# Lixieuhr_Master.net
KiCad netlist of a schematic drawn in EAGLE
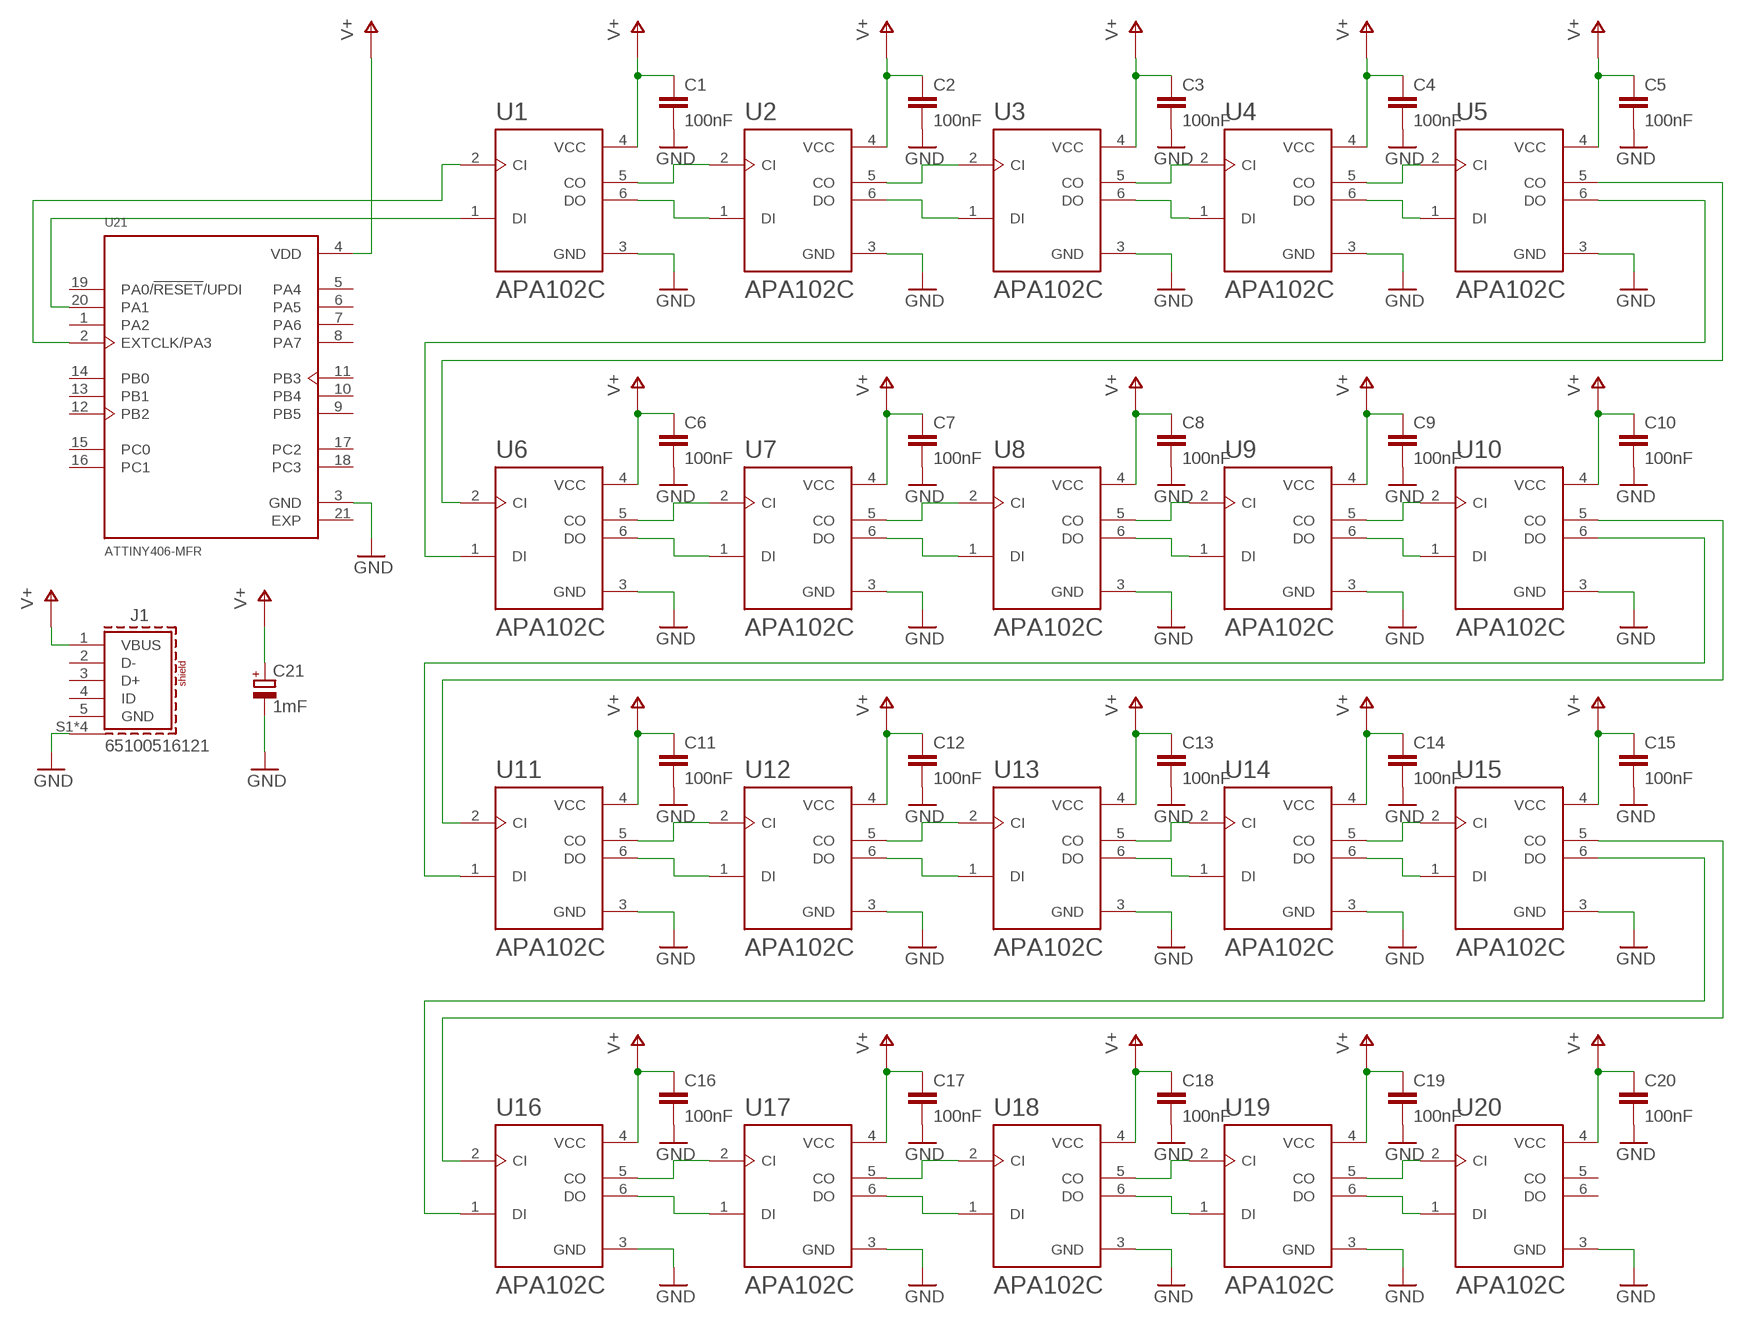
[diagram p0: schematic, sheet 1]

(export (version "E")
  (design (tool "Eeschema 10.0.6"))
  (components
    (comp (ref "C1")
      (value "100nF")
      (footprint "eagle-import:C0805")
      (libsource (lib "eagle-import") (part "C-0805"))
    )
    (comp (ref "C2")
      (value "100nF")
      (footprint "eagle-import:C0805")
      (libsource (lib "eagle-import") (part "C-0805"))
    )
    (comp (ref "C3")
      (value "100nF")
      (footprint "eagle-import:C0805")
      (libsource (lib "eagle-import") (part "C-0805"))
    )
    (comp (ref "C4")
      (value "100nF")
      (footprint "eagle-import:C0805")
      (libsource (lib "eagle-import") (part "C-0805"))
    )
    (comp (ref "C5")
      (value "100nF")
      (footprint "eagle-import:C0805")
      (libsource (lib "eagle-import") (part "C-0805"))
    )
    (comp (ref "C6")
      (value "100nF")
      (footprint "eagle-import:C0805")
      (libsource (lib "eagle-import") (part "C-0805"))
    )
    (comp (ref "C7")
      (value "100nF")
      (footprint "eagle-import:C0805")
      (libsource (lib "eagle-import") (part "C-0805"))
    )
    (comp (ref "C8")
      (value "100nF")
      (footprint "eagle-import:C0805")
      (libsource (lib "eagle-import") (part "C-0805"))
    )
    (comp (ref "C9")
      (value "100nF")
      (footprint "eagle-import:C0805")
      (libsource (lib "eagle-import") (part "C-0805"))
    )
    (comp (ref "C10")
      (value "100nF")
      (footprint "eagle-import:C0805")
      (libsource (lib "eagle-import") (part "C-0805"))
    )
    (comp (ref "C11")
      (value "100nF")
      (footprint "eagle-import:C0805")
      (libsource (lib "eagle-import") (part "C-0805"))
    )
    (comp (ref "C12")
      (value "100nF")
      (footprint "eagle-import:C0805")
      (libsource (lib "eagle-import") (part "C-0805"))
    )
    (comp (ref "C13")
      (value "100nF")
      (footprint "eagle-import:C0805")
      (libsource (lib "eagle-import") (part "C-0805"))
    )
    (comp (ref "C14")
      (value "100nF")
      (footprint "eagle-import:C0805")
      (libsource (lib "eagle-import") (part "C-0805"))
    )
    (comp (ref "C15")
      (value "100nF")
      (footprint "eagle-import:C0805")
      (libsource (lib "eagle-import") (part "C-0805"))
    )
    (comp (ref "C16")
      (value "100nF")
      (footprint "eagle-import:C0805")
      (libsource (lib "eagle-import") (part "C-0805"))
    )
    (comp (ref "C17")
      (value "100nF")
      (footprint "eagle-import:C0805")
      (libsource (lib "eagle-import") (part "C-0805"))
    )
    (comp (ref "C18")
      (value "100nF")
      (footprint "eagle-import:C0805")
      (libsource (lib "eagle-import") (part "C-0805"))
    )
    (comp (ref "C19")
      (value "100nF")
      (footprint "eagle-import:C0805")
      (libsource (lib "eagle-import") (part "C-0805"))
    )
    (comp (ref "C20")
      (value "100nF")
      (footprint "eagle-import:C0805")
      (libsource (lib "eagle-import") (part "C-0805"))
    )
    (comp (ref "C21")
      (value "1mF")
      (footprint "eagle-import:E5-8,5")
      (libsource (lib "eagle-import") (part "CPOL-EUE5-8.5"))
    )
    (comp (ref "J1")
      (value "65100516121")
      (footprint "eagle-import:65100516121")
      (fields (field (name "MF") "Würth Elektronik"))
      (libsource (lib "eagle-import") (part "65100516121"))
    )
    (comp (ref "U1")
      (value "APA102C")
      (footprint "eagle-import:SON160P500X500X140-6N")
      (fields (field (name "MF") "Shiji Lighting"))
      (libsource (lib "eagle-import") (part "APA102C"))
    )
    (comp (ref "U2")
      (value "APA102C")
      (footprint "eagle-import:SON160P500X500X140-6N")
      (fields (field (name "MF") "Shiji Lighting"))
      (libsource (lib "eagle-import") (part "APA102C"))
    )
    (comp (ref "U3")
      (value "APA102C")
      (footprint "eagle-import:SON160P500X500X140-6N")
      (fields (field (name "MF") "Shiji Lighting"))
      (libsource (lib "eagle-import") (part "APA102C"))
    )
    (comp (ref "U4")
      (value "APA102C")
      (footprint "eagle-import:SON160P500X500X140-6N")
      (fields (field (name "MF") "Shiji Lighting"))
      (libsource (lib "eagle-import") (part "APA102C"))
    )
    (comp (ref "U5")
      (value "APA102C")
      (footprint "eagle-import:SON160P500X500X140-6N")
      (fields (field (name "MF") "Shiji Lighting"))
      (libsource (lib "eagle-import") (part "APA102C"))
    )
    (comp (ref "U6")
      (value "APA102C")
      (footprint "eagle-import:SON160P500X500X140-6N")
      (fields (field (name "MF") "Shiji Lighting"))
      (libsource (lib "eagle-import") (part "APA102C"))
    )
    (comp (ref "U7")
      (value "APA102C")
      (footprint "eagle-import:SON160P500X500X140-6N")
      (fields (field (name "MF") "Shiji Lighting"))
      (libsource (lib "eagle-import") (part "APA102C"))
    )
    (comp (ref "U8")
      (value "APA102C")
      (footprint "eagle-import:SON160P500X500X140-6N")
      (fields (field (name "MF") "Shiji Lighting"))
      (libsource (lib "eagle-import") (part "APA102C"))
    )
    (comp (ref "U9")
      (value "APA102C")
      (footprint "eagle-import:SON160P500X500X140-6N")
      (fields (field (name "MF") "Shiji Lighting"))
      (libsource (lib "eagle-import") (part "APA102C"))
    )
    (comp (ref "U10")
      (value "APA102C")
      (footprint "eagle-import:SON160P500X500X140-6N")
      (fields (field (name "MF") "Shiji Lighting"))
      (libsource (lib "eagle-import") (part "APA102C"))
    )
    (comp (ref "U11")
      (value "APA102C")
      (footprint "eagle-import:SON160P500X500X140-6N")
      (fields (field (name "MF") "Shiji Lighting"))
      (libsource (lib "eagle-import") (part "APA102C"))
    )
    (comp (ref "U12")
      (value "APA102C")
      (footprint "eagle-import:SON160P500X500X140-6N")
      (fields (field (name "MF") "Shiji Lighting"))
      (libsource (lib "eagle-import") (part "APA102C"))
    )
    (comp (ref "U13")
      (value "APA102C")
      (footprint "eagle-import:SON160P500X500X140-6N")
      (fields (field (name "MF") "Shiji Lighting"))
      (libsource (lib "eagle-import") (part "APA102C"))
    )
    (comp (ref "U14")
      (value "APA102C")
      (footprint "eagle-import:SON160P500X500X140-6N")
      (fields (field (name "MF") "Shiji Lighting"))
      (libsource (lib "eagle-import") (part "APA102C"))
    )
    (comp (ref "U15")
      (value "APA102C")
      (footprint "eagle-import:SON160P500X500X140-6N")
      (fields (field (name "MF") "Shiji Lighting"))
      (libsource (lib "eagle-import") (part "APA102C"))
    )
    (comp (ref "U16")
      (value "APA102C")
      (footprint "eagle-import:SON160P500X500X140-6N")
      (fields (field (name "MF") "Shiji Lighting"))
      (libsource (lib "eagle-import") (part "APA102C"))
    )
    (comp (ref "U17")
      (value "APA102C")
      (footprint "eagle-import:SON160P500X500X140-6N")
      (fields (field (name "MF") "Shiji Lighting"))
      (libsource (lib "eagle-import") (part "APA102C"))
    )
    (comp (ref "U18")
      (value "APA102C")
      (footprint "eagle-import:SON160P500X500X140-6N")
      (fields (field (name "MF") "Shiji Lighting"))
      (libsource (lib "eagle-import") (part "APA102C"))
    )
    (comp (ref "U19")
      (value "APA102C")
      (footprint "eagle-import:SON160P500X500X140-6N")
      (fields (field (name "MF") "Shiji Lighting"))
      (libsource (lib "eagle-import") (part "APA102C"))
    )
    (comp (ref "U20")
      (value "APA102C")
      (footprint "eagle-import:SON160P500X500X140-6N")
      (fields (field (name "MF") "Shiji Lighting"))
      (libsource (lib "eagle-import") (part "APA102C"))
    )
    (comp (ref "U21")
      (value "ATTINY406-MFR")
      (footprint "eagle-import:QFN40P300X300X90-21N")
      (fields (field (name "MF") "Microchip"))
      (libsource (lib "eagle-import") (part "ATTINY406-MFR"))
    )
  )
  (nets
    (net (code "1") (name "/EXP") (class "Default")
      (node (ref "U21") (pin "21") (pinfunction "EXP_21") (pintype "power_in"))
    )
    (net (code "2") (name "GND") (class "Default")
      (node (ref "C1") (pin "2") (pinfunction "2_2") (pintype "passive"))
      (node (ref "C10") (pin "2") (pinfunction "2_2") (pintype "passive"))
      (node (ref "C11") (pin "2") (pinfunction "2_2") (pintype "passive"))
      (node (ref "C12") (pin "2") (pinfunction "2_2") (pintype "passive"))
      (node (ref "C13") (pin "2") (pinfunction "2_2") (pintype "passive"))
      (node (ref "C14") (pin "2") (pinfunction "2_2") (pintype "passive"))
      (node (ref "C15") (pin "2") (pinfunction "2_2") (pintype "passive"))
      (node (ref "C16") (pin "2") (pinfunction "2_2") (pintype "passive"))
      (node (ref "C17") (pin "2") (pinfunction "2_2") (pintype "passive"))
      (node (ref "C18") (pin "2") (pinfunction "2_2") (pintype "passive"))
      (node (ref "C19") (pin "2") (pinfunction "2_2") (pintype "passive"))
      (node (ref "C2") (pin "2") (pinfunction "2_2") (pintype "passive"))
      (node (ref "C20") (pin "2") (pinfunction "2_2") (pintype "passive"))
      (node (ref "C21") (pin "-") (pinfunction "-_-") (pintype "passive"))
      (node (ref "C3") (pin "2") (pinfunction "2_2") (pintype "passive"))
      (node (ref "C4") (pin "2") (pinfunction "2_2") (pintype "passive"))
      (node (ref "C5") (pin "2") (pinfunction "2_2") (pintype "passive"))
      (node (ref "C6") (pin "2") (pinfunction "2_2") (pintype "passive"))
      (node (ref "C7") (pin "2") (pinfunction "2_2") (pintype "passive"))
      (node (ref "C8") (pin "2") (pinfunction "2_2") (pintype "passive"))
      (node (ref "C9") (pin "2") (pinfunction "2_2") (pintype "passive"))
      (node (ref "J1") (pin "S1") (pinfunction "SHIELD_S1") (pintype "passive"))
      (node (ref "J1") (pin "S2") (pinfunction "SHIELD_S2") (pintype "passive"))
      (node (ref "J1") (pin "S3") (pinfunction "SHIELD_S3") (pintype "passive"))
      (node (ref "J1") (pin "S4") (pinfunction "SHIELD_S4") (pintype "passive"))
      (node (ref "U1") (pin "3") (pinfunction "GND_3") (pintype "power_in"))
      (node (ref "U10") (pin "3") (pinfunction "GND_3") (pintype "power_in"))
      (node (ref "U11") (pin "3") (pinfunction "GND_3") (pintype "power_in"))
      (node (ref "U12") (pin "3") (pinfunction "GND_3") (pintype "power_in"))
      (node (ref "U13") (pin "3") (pinfunction "GND_3") (pintype "power_in"))
      (node (ref "U14") (pin "3") (pinfunction "GND_3") (pintype "power_in"))
      (node (ref "U15") (pin "3") (pinfunction "GND_3") (pintype "power_in"))
      (node (ref "U16") (pin "3") (pinfunction "GND_3") (pintype "power_in"))
      (node (ref "U17") (pin "3") (pinfunction "GND_3") (pintype "power_in"))
      (node (ref "U18") (pin "3") (pinfunction "GND_3") (pintype "power_in"))
      (node (ref "U19") (pin "3") (pinfunction "GND_3") (pintype "power_in"))
      (node (ref "U2") (pin "3") (pinfunction "GND_3") (pintype "power_in"))
      (node (ref "U20") (pin "3") (pinfunction "GND_3") (pintype "power_in"))
      (node (ref "U21") (pin "3") (pinfunction "GND_3") (pintype "power_in"))
      (node (ref "U3") (pin "3") (pinfunction "GND_3") (pintype "power_in"))
      (node (ref "U4") (pin "3") (pinfunction "GND_3") (pintype "power_in"))
      (node (ref "U5") (pin "3") (pinfunction "GND_3") (pintype "power_in"))
      (node (ref "U6") (pin "3") (pinfunction "GND_3") (pintype "power_in"))
      (node (ref "U7") (pin "3") (pinfunction "GND_3") (pintype "power_in"))
      (node (ref "U8") (pin "3") (pinfunction "GND_3") (pintype "power_in"))
      (node (ref "U9") (pin "3") (pinfunction "GND_3") (pintype "power_in"))
    )
    (net (code "3") (name "Net-(U1-CI)") (class "Default")
      (node (ref "U1") (pin "2") (pinfunction "CI_2") (pintype "input"))
      (node (ref "U21") (pin "2") (pinfunction "EXTCLK/PA3_2") (pintype "bidirectional"))
    )
    (net (code "4") (name "Net-(U1-CO)") (class "Default")
      (node (ref "U1") (pin "5") (pinfunction "CO_5") (pintype "output"))
      (node (ref "U2") (pin "2") (pinfunction "CI_2") (pintype "input"))
    )
    (net (code "5") (name "Net-(U1-DI)") (class "Default")
      (node (ref "U1") (pin "1") (pinfunction "DI_1") (pintype "input"))
      (node (ref "U21") (pin "20") (pinfunction "PA1_20") (pintype "bidirectional"))
    )
    (net (code "6") (name "Net-(U1-DO)") (class "Default")
      (node (ref "U1") (pin "6") (pinfunction "DO_6") (pintype "output"))
      (node (ref "U2") (pin "1") (pinfunction "DI_1") (pintype "input"))
    )
    (net (code "7") (name "Net-(U2-CO)") (class "Default")
      (node (ref "U2") (pin "5") (pinfunction "CO_5") (pintype "output"))
      (node (ref "U3") (pin "2") (pinfunction "CI_2") (pintype "input"))
    )
    (net (code "8") (name "Net-(U2-DO)") (class "Default")
      (node (ref "U2") (pin "6") (pinfunction "DO_6") (pintype "output"))
      (node (ref "U3") (pin "1") (pinfunction "DI_1") (pintype "input"))
    )
    (net (code "9") (name "Net-(U3-CO)") (class "Default")
      (node (ref "U3") (pin "5") (pinfunction "CO_5") (pintype "output"))
      (node (ref "U4") (pin "2") (pinfunction "CI_2") (pintype "input"))
    )
    (net (code "10") (name "Net-(U3-DO)") (class "Default")
      (node (ref "U3") (pin "6") (pinfunction "DO_6") (pintype "output"))
      (node (ref "U4") (pin "1") (pinfunction "DI_1") (pintype "input"))
    )
    (net (code "11") (name "Net-(U4-CO)") (class "Default")
      (node (ref "U4") (pin "5") (pinfunction "CO_5") (pintype "output"))
      (node (ref "U5") (pin "2") (pinfunction "CI_2") (pintype "input"))
    )
    (net (code "12") (name "Net-(U4-DO)") (class "Default")
      (node (ref "U4") (pin "6") (pinfunction "DO_6") (pintype "output"))
      (node (ref "U5") (pin "1") (pinfunction "DI_1") (pintype "input"))
    )
    (net (code "13") (name "Net-(U5-CO)") (class "Default")
      (node (ref "U5") (pin "5") (pinfunction "CO_5") (pintype "output"))
      (node (ref "U6") (pin "2") (pinfunction "CI_2") (pintype "input"))
    )
    (net (code "14") (name "Net-(U5-DO)") (class "Default")
      (node (ref "U5") (pin "6") (pinfunction "DO_6") (pintype "output"))
      (node (ref "U6") (pin "1") (pinfunction "DI_1") (pintype "input"))
    )
    (net (code "15") (name "Net-(U6-CO)") (class "Default")
      (node (ref "U6") (pin "5") (pinfunction "CO_5") (pintype "output"))
      (node (ref "U7") (pin "2") (pinfunction "CI_2") (pintype "input"))
    )
    (net (code "16") (name "Net-(U6-DO)") (class "Default")
      (node (ref "U6") (pin "6") (pinfunction "DO_6") (pintype "output"))
      (node (ref "U7") (pin "1") (pinfunction "DI_1") (pintype "input"))
    )
    (net (code "17") (name "Net-(U7-CO)") (class "Default")
      (node (ref "U7") (pin "5") (pinfunction "CO_5") (pintype "output"))
      (node (ref "U8") (pin "2") (pinfunction "CI_2") (pintype "input"))
    )
    (net (code "18") (name "Net-(U7-DO)") (class "Default")
      (node (ref "U7") (pin "6") (pinfunction "DO_6") (pintype "output"))
      (node (ref "U8") (pin "1") (pinfunction "DI_1") (pintype "input"))
    )
    (net (code "19") (name "Net-(U8-CO)") (class "Default")
      (node (ref "U8") (pin "5") (pinfunction "CO_5") (pintype "output"))
      (node (ref "U9") (pin "2") (pinfunction "CI_2") (pintype "input"))
    )
    (net (code "20") (name "Net-(U8-DO)") (class "Default")
      (node (ref "U8") (pin "6") (pinfunction "DO_6") (pintype "output"))
      (node (ref "U9") (pin "1") (pinfunction "DI_1") (pintype "input"))
    )
    (net (code "21") (name "Net-(U10-CI)") (class "Default")
      (node (ref "U10") (pin "2") (pinfunction "CI_2") (pintype "input"))
      (node (ref "U9") (pin "5") (pinfunction "CO_5") (pintype "output"))
    )
    (net (code "22") (name "Net-(U10-CO)") (class "Default")
      (node (ref "U10") (pin "5") (pinfunction "CO_5") (pintype "output"))
      (node (ref "U11") (pin "2") (pinfunction "CI_2") (pintype "input"))
    )
    (net (code "23") (name "Net-(U10-DI)") (class "Default")
      (node (ref "U10") (pin "1") (pinfunction "DI_1") (pintype "input"))
      (node (ref "U9") (pin "6") (pinfunction "DO_6") (pintype "output"))
    )
    (net (code "24") (name "Net-(U10-DO)") (class "Default")
      (node (ref "U10") (pin "6") (pinfunction "DO_6") (pintype "output"))
      (node (ref "U11") (pin "1") (pinfunction "DI_1") (pintype "input"))
    )
    (net (code "25") (name "Net-(U11-CO)") (class "Default")
      (node (ref "U11") (pin "5") (pinfunction "CO_5") (pintype "output"))
      (node (ref "U12") (pin "2") (pinfunction "CI_2") (pintype "input"))
    )
    (net (code "26") (name "Net-(U11-DO)") (class "Default")
      (node (ref "U11") (pin "6") (pinfunction "DO_6") (pintype "output"))
      (node (ref "U12") (pin "1") (pinfunction "DI_1") (pintype "input"))
    )
    (net (code "27") (name "Net-(U12-CO)") (class "Default")
      (node (ref "U12") (pin "5") (pinfunction "CO_5") (pintype "output"))
      (node (ref "U13") (pin "2") (pinfunction "CI_2") (pintype "input"))
    )
    (net (code "28") (name "Net-(U12-DO)") (class "Default")
      (node (ref "U12") (pin "6") (pinfunction "DO_6") (pintype "output"))
      (node (ref "U13") (pin "1") (pinfunction "DI_1") (pintype "input"))
    )
    (net (code "29") (name "Net-(U13-CO)") (class "Default")
      (node (ref "U13") (pin "5") (pinfunction "CO_5") (pintype "output"))
      (node (ref "U14") (pin "2") (pinfunction "CI_2") (pintype "input"))
    )
    (net (code "30") (name "Net-(U13-DO)") (class "Default")
      (node (ref "U13") (pin "6") (pinfunction "DO_6") (pintype "output"))
      (node (ref "U14") (pin "1") (pinfunction "DI_1") (pintype "input"))
    )
    (net (code "31") (name "Net-(U14-CO)") (class "Default")
      (node (ref "U14") (pin "5") (pinfunction "CO_5") (pintype "output"))
      (node (ref "U15") (pin "2") (pinfunction "CI_2") (pintype "input"))
    )
    (net (code "32") (name "Net-(U14-DO)") (class "Default")
      (node (ref "U14") (pin "6") (pinfunction "DO_6") (pintype "output"))
      (node (ref "U15") (pin "1") (pinfunction "DI_1") (pintype "input"))
    )
    (net (code "33") (name "Net-(U15-CO)") (class "Default")
      (node (ref "U15") (pin "5") (pinfunction "CO_5") (pintype "output"))
      (node (ref "U16") (pin "2") (pinfunction "CI_2") (pintype "input"))
    )
    (net (code "34") (name "Net-(U15-DO)") (class "Default")
      (node (ref "U15") (pin "6") (pinfunction "DO_6") (pintype "output"))
      (node (ref "U16") (pin "1") (pinfunction "DI_1") (pintype "input"))
    )
    (net (code "35") (name "Net-(U16-CO)") (class "Default")
      (node (ref "U16") (pin "5") (pinfunction "CO_5") (pintype "output"))
      (node (ref "U17") (pin "2") (pinfunction "CI_2") (pintype "input"))
    )
    (net (code "36") (name "Net-(U16-DO)") (class "Default")
      (node (ref "U16") (pin "6") (pinfunction "DO_6") (pintype "output"))
      (node (ref "U17") (pin "1") (pinfunction "DI_1") (pintype "input"))
    )
    (net (code "37") (name "Net-(U17-CO)") (class "Default")
      (node (ref "U17") (pin "5") (pinfunction "CO_5") (pintype "output"))
      (node (ref "U18") (pin "2") (pinfunction "CI_2") (pintype "input"))
    )
    (net (code "38") (name "Net-(U17-DO)") (class "Default")
      (node (ref "U17") (pin "6") (pinfunction "DO_6") (pintype "output"))
      (node (ref "U18") (pin "1") (pinfunction "DI_1") (pintype "input"))
    )
    (net (code "39") (name "Net-(U18-CO)") (class "Default")
      (node (ref "U18") (pin "5") (pinfunction "CO_5") (pintype "output"))
      (node (ref "U19") (pin "2") (pinfunction "CI_2") (pintype "input"))
    )
    (net (code "40") (name "Net-(U18-DO)") (class "Default")
      (node (ref "U18") (pin "6") (pinfunction "DO_6") (pintype "output"))
      (node (ref "U19") (pin "1") (pinfunction "DI_1") (pintype "input"))
    )
    (net (code "41") (name "Net-(U19-CO)") (class "Default")
      (node (ref "U19") (pin "5") (pinfunction "CO_5") (pintype "output"))
      (node (ref "U20") (pin "2") (pinfunction "CI_2") (pintype "input"))
    )
    (net (code "42") (name "Net-(U19-DO)") (class "Default")
      (node (ref "U19") (pin "6") (pinfunction "DO_6") (pintype "output"))
      (node (ref "U20") (pin "1") (pinfunction "DI_1") (pintype "input"))
    )
    (net (code "43") (name "V+") (class "Default")
      (node (ref "C1") (pin "1") (pinfunction "1_1") (pintype "passive"))
      (node (ref "C10") (pin "1") (pinfunction "1_1") (pintype "passive"))
      (node (ref "C11") (pin "1") (pinfunction "1_1") (pintype "passive"))
      (node (ref "C12") (pin "1") (pinfunction "1_1") (pintype "passive"))
      (node (ref "C13") (pin "1") (pinfunction "1_1") (pintype "passive"))
      (node (ref "C14") (pin "1") (pinfunction "1_1") (pintype "passive"))
      (node (ref "C15") (pin "1") (pinfunction "1_1") (pintype "passive"))
      (node (ref "C16") (pin "1") (pinfunction "1_1") (pintype "passive"))
      (node (ref "C17") (pin "1") (pinfunction "1_1") (pintype "passive"))
      (node (ref "C18") (pin "1") (pinfunction "1_1") (pintype "passive"))
      (node (ref "C19") (pin "1") (pinfunction "1_1") (pintype "passive"))
      (node (ref "C2") (pin "1") (pinfunction "1_1") (pintype "passive"))
      (node (ref "C20") (pin "1") (pinfunction "1_1") (pintype "passive"))
      (node (ref "C21") (pin "+") (pinfunction "+_+") (pintype "passive"))
      (node (ref "C3") (pin "1") (pinfunction "1_1") (pintype "passive"))
      (node (ref "C4") (pin "1") (pinfunction "1_1") (pintype "passive"))
      (node (ref "C5") (pin "1") (pinfunction "1_1") (pintype "passive"))
      (node (ref "C6") (pin "1") (pinfunction "1_1") (pintype "passive"))
      (node (ref "C7") (pin "1") (pinfunction "1_1") (pintype "passive"))
      (node (ref "C8") (pin "1") (pinfunction "1_1") (pintype "passive"))
      (node (ref "C9") (pin "1") (pinfunction "1_1") (pintype "passive"))
      (node (ref "J1") (pin "1") (pinfunction "VBUS_1") (pintype "passive"))
      (node (ref "U1") (pin "4") (pinfunction "VCC_4") (pintype "power_in"))
      (node (ref "U10") (pin "4") (pinfunction "VCC_4") (pintype "power_in"))
      (node (ref "U11") (pin "4") (pinfunction "VCC_4") (pintype "power_in"))
      (node (ref "U12") (pin "4") (pinfunction "VCC_4") (pintype "power_in"))
      (node (ref "U13") (pin "4") (pinfunction "VCC_4") (pintype "power_in"))
      (node (ref "U14") (pin "4") (pinfunction "VCC_4") (pintype "power_in"))
      (node (ref "U15") (pin "4") (pinfunction "VCC_4") (pintype "power_in"))
      (node (ref "U16") (pin "4") (pinfunction "VCC_4") (pintype "power_in"))
      (node (ref "U17") (pin "4") (pinfunction "VCC_4") (pintype "power_in"))
      (node (ref "U18") (pin "4") (pinfunction "VCC_4") (pintype "power_in"))
      (node (ref "U19") (pin "4") (pinfunction "VCC_4") (pintype "power_in"))
      (node (ref "U2") (pin "4") (pinfunction "VCC_4") (pintype "power_in"))
      (node (ref "U20") (pin "4") (pinfunction "VCC_4") (pintype "power_in"))
      (node (ref "U21") (pin "4") (pinfunction "VDD_4") (pintype "power_in"))
      (node (ref "U3") (pin "4") (pinfunction "VCC_4") (pintype "power_in"))
      (node (ref "U4") (pin "4") (pinfunction "VCC_4") (pintype "power_in"))
      (node (ref "U5") (pin "4") (pinfunction "VCC_4") (pintype "power_in"))
      (node (ref "U6") (pin "4") (pinfunction "VCC_4") (pintype "power_in"))
      (node (ref "U7") (pin "4") (pinfunction "VCC_4") (pintype "power_in"))
      (node (ref "U8") (pin "4") (pinfunction "VCC_4") (pintype "power_in"))
      (node (ref "U9") (pin "4") (pinfunction "VCC_4") (pintype "power_in"))
    )
    (net (code "44") (name "unconnected-(J1-D+-Pad3)") (class "Default")
      (node (ref "J1") (pin "3") (pinfunction "D+_3") (pintype "passive"))
    )
    (net (code "45") (name "unconnected-(J1-D--Pad2)") (class "Default")
      (node (ref "J1") (pin "2") (pinfunction "D-_2") (pintype "passive"))
    )
    (net (code "46") (name "unconnected-(J1-GND-Pad5)") (class "Default")
      (node (ref "J1") (pin "5") (pinfunction "GND_5") (pintype "passive"))
    )
    (net (code "47") (name "unconnected-(J1-ID-Pad4)") (class "Default")
      (node (ref "J1") (pin "4") (pinfunction "ID_4") (pintype "passive"))
    )
    (net (code "48") (name "unconnected-(U20-CO-Pad5)") (class "Default")
      (node (ref "U20") (pin "5") (pinfunction "CO_5") (pintype "output"))
    )
    (net (code "49") (name "unconnected-(U20-DO-Pad6)") (class "Default")
      (node (ref "U20") (pin "6") (pinfunction "DO_6") (pintype "output"))
    )
    (net (code "50") (name "unconnected-(U21-PA0{slash}~{RESET}{slash}UPDI-Pad19)") (class "Default")
      (node (ref "U21") (pin "19") (pinfunction "PA0/~{RESET}/UPDI_19") (pintype "bidirectional"))
    )
    (net (code "51") (name "unconnected-(U21-PA2-Pad1)") (class "Default")
      (node (ref "U21") (pin "1") (pinfunction "PA2_1") (pintype "bidirectional"))
    )
    (net (code "52") (name "unconnected-(U21-PA4-Pad5)") (class "Default")
      (node (ref "U21") (pin "5") (pinfunction "PA4_5") (pintype "bidirectional"))
    )
    (net (code "53") (name "unconnected-(U21-PA5-Pad6)") (class "Default")
      (node (ref "U21") (pin "6") (pinfunction "PA5_6") (pintype "bidirectional"))
    )
    (net (code "54") (name "unconnected-(U21-PA6-Pad7)") (class "Default")
      (node (ref "U21") (pin "7") (pinfunction "PA6_7") (pintype "bidirectional"))
    )
    (net (code "55") (name "unconnected-(U21-PA7-Pad8)") (class "Default")
      (node (ref "U21") (pin "8") (pinfunction "PA7_8") (pintype "bidirectional"))
    )
    (net (code "56") (name "unconnected-(U21-PB0-Pad14)") (class "Default")
      (node (ref "U21") (pin "14") (pinfunction "PB0_14") (pintype "bidirectional"))
    )
    (net (code "57") (name "unconnected-(U21-PB1-Pad13)") (class "Default")
      (node (ref "U21") (pin "13") (pinfunction "PB1_13") (pintype "bidirectional"))
    )
    (net (code "58") (name "unconnected-(U21-PB2-Pad12)") (class "Default")
      (node (ref "U21") (pin "12") (pinfunction "PB2_12") (pintype "bidirectional"))
    )
    (net (code "59") (name "unconnected-(U21-PB3-Pad11)") (class "Default")
      (node (ref "U21") (pin "11") (pinfunction "PB3_11") (pintype "bidirectional"))
    )
    (net (code "60") (name "unconnected-(U21-PB4-Pad10)") (class "Default")
      (node (ref "U21") (pin "10") (pinfunction "PB4_10") (pintype "bidirectional"))
    )
    (net (code "61") (name "unconnected-(U21-PB5-Pad9)") (class "Default")
      (node (ref "U21") (pin "9") (pinfunction "PB5_9") (pintype "bidirectional"))
    )
    (net (code "62") (name "unconnected-(U21-PC0-Pad15)") (class "Default")
      (node (ref "U21") (pin "15") (pinfunction "PC0_15") (pintype "bidirectional"))
    )
    (net (code "63") (name "unconnected-(U21-PC1-Pad16)") (class "Default")
      (node (ref "U21") (pin "16") (pinfunction "PC1_16") (pintype "bidirectional"))
    )
    (net (code "64") (name "unconnected-(U21-PC2-Pad17)") (class "Default")
      (node (ref "U21") (pin "17") (pinfunction "PC2_17") (pintype "bidirectional"))
    )
    (net (code "65") (name "unconnected-(U21-PC3-Pad18)") (class "Default")
      (node (ref "U21") (pin "18") (pinfunction "PC3_18") (pintype "bidirectional"))
    )
  )
)
